# relais_platine_simplified.net
KiCad netlist of a schematic drawn in EAGLE
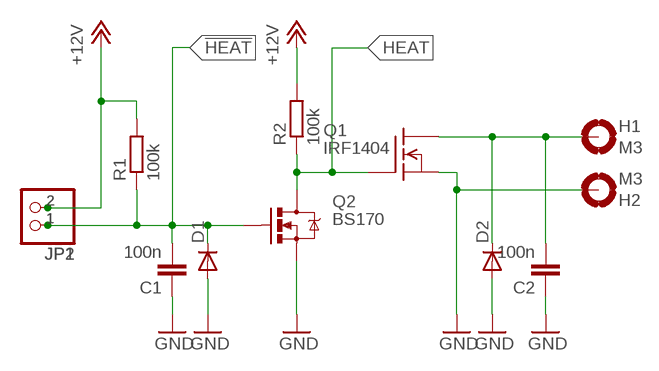
[diagram p0: schematic, sheet 1]

(export (version "E")
  (design (tool "Eeschema 10.0.6"))
  (components
    (comp (ref "C1")
      (value "100n")
      (footprint "eagle-import:C0805K")
      (libsource (lib "eagle-import") (part "C-EUC0805K"))
    )
    (comp (ref "C2")
      (value "100n")
      (footprint "eagle-import:C0805K")
      (libsource (lib "eagle-import") (part "C-EUC0805K"))
    )
    (comp (ref "D1")
      (value "DIODE-MINIMELF")
      (footprint "eagle-import:MINIMELF")
      (libsource (lib "eagle-import") (part "DIODE-MINIMELF"))
    )
    (comp (ref "D2")
      (value "DIODE-MINIMELF")
      (footprint "eagle-import:MINIMELF")
      (libsource (lib "eagle-import") (part "DIODE-MINIMELF"))
    )
    (comp (ref "H1")
      (value "M3")
      (footprint "eagle-import:3,0-PAD")
      (libsource (lib "eagle-import") (part "MOUNT-PAD-ROUND3.0"))
    )
    (comp (ref "H2")
      (value "M3")
      (footprint "eagle-import:3,0-PAD")
      (libsource (lib "eagle-import") (part "MOUNT-PAD-ROUND3.0"))
    )
    (comp (ref "JP1")
      (value "PINHD-1X2")
      (footprint "eagle-import:1X02")
      (libsource (lib "eagle-import") (part "PINHD-1X2"))
    )
    (comp (ref "JP2")
      (value "PINHD-1X2/90")
      (footprint "eagle-import:1X02_90")
      (libsource (lib "eagle-import") (part "PINHD-1X2/90"))
    )
    (comp (ref "Q1")
      (value "IRF1404")
      (footprint "eagle-import:TO220")
      (libsource (lib "eagle-import") (part "IRF540"))
    )
    (comp (ref "Q2")
      (value "BS170")
      (footprint "eagle-import:SOT23-3")
      (libsource (lib "eagle-import") (part "MOSFET-NCHANNELBSS123LT1G"))
    )
    (comp (ref "R1")
      (value "100k")
      (footprint "eagle-import:M0805")
      (libsource (lib "eagle-import") (part "R-EU_M0805"))
    )
    (comp (ref "R2")
      (value "100k")
      (footprint "eagle-import:M0805")
      (libsource (lib "eagle-import") (part "R-EU_M0805"))
    )
  )
  (nets
    (net (code "1") (name "+12V") (class "Default")
      (node (ref "JP1") (pin "2") (pinfunction "2_2") (pintype "passive"))
      (node (ref "JP2") (pin "2") (pinfunction "2_2") (pintype "passive"))
      (node (ref "R1") (pin "2") (pinfunction "2_2") (pintype "passive"))
      (node (ref "R2") (pin "2") (pinfunction "2_2") (pintype "passive"))
    )
    (net (code "2") (name "/~{HEAT}") (class "Default")
      (node (ref "C1") (pin "2") (pinfunction "2_2") (pintype "passive"))
      (node (ref "D1") (pin "C") (pinfunction "C_C") (pintype "passive"))
      (node (ref "JP1") (pin "1") (pinfunction "1_1") (pintype "passive"))
      (node (ref "JP2") (pin "1") (pinfunction "1_1") (pintype "passive"))
      (node (ref "Q2") (pin "1") (pinfunction "G_1") (pintype "passive"))
      (node (ref "R1") (pin "1") (pinfunction "1_1") (pintype "passive"))
    )
    (net (code "3") (name "GND") (class "Default")
      (node (ref "C1") (pin "1") (pinfunction "1_1") (pintype "passive"))
      (node (ref "C2") (pin "1") (pinfunction "1_1") (pintype "passive"))
      (node (ref "D1") (pin "A") (pinfunction "A_A") (pintype "passive"))
      (node (ref "D2") (pin "A") (pinfunction "A_A") (pintype "passive"))
      (node (ref "H2") (pin "B3,0") (pinfunction "MOUNT_B3,0") (pintype "passive"))
      (node (ref "Q1") (pin "3") (pinfunction "S_3") (pintype "passive"))
      (node (ref "Q2") (pin "2") (pinfunction "S_2") (pintype "passive"))
    )
    (net (code "4") (name "HEAT") (class "Default")
      (node (ref "Q1") (pin "1") (pinfunction "G_1") (pintype "passive"))
      (node (ref "Q2") (pin "3") (pinfunction "D_3") (pintype "passive"))
      (node (ref "R2") (pin "1") (pinfunction "1_1") (pintype "passive"))
    )
    (net (code "5") (name "Net-(H1-MOUNT)") (class "Default")
      (node (ref "C2") (pin "2") (pinfunction "2_2") (pintype "passive"))
      (node (ref "D2") (pin "C") (pinfunction "C_C") (pintype "passive"))
      (node (ref "H1") (pin "B3,0") (pinfunction "MOUNT_B3,0") (pintype "passive"))
      (node (ref "Q1") (pin "2") (pinfunction "D_2") (pintype "passive"))
    )
  )
)
